# IGVC_breakout_board.net
KiCad netlist of a schematic drawn in EAGLE
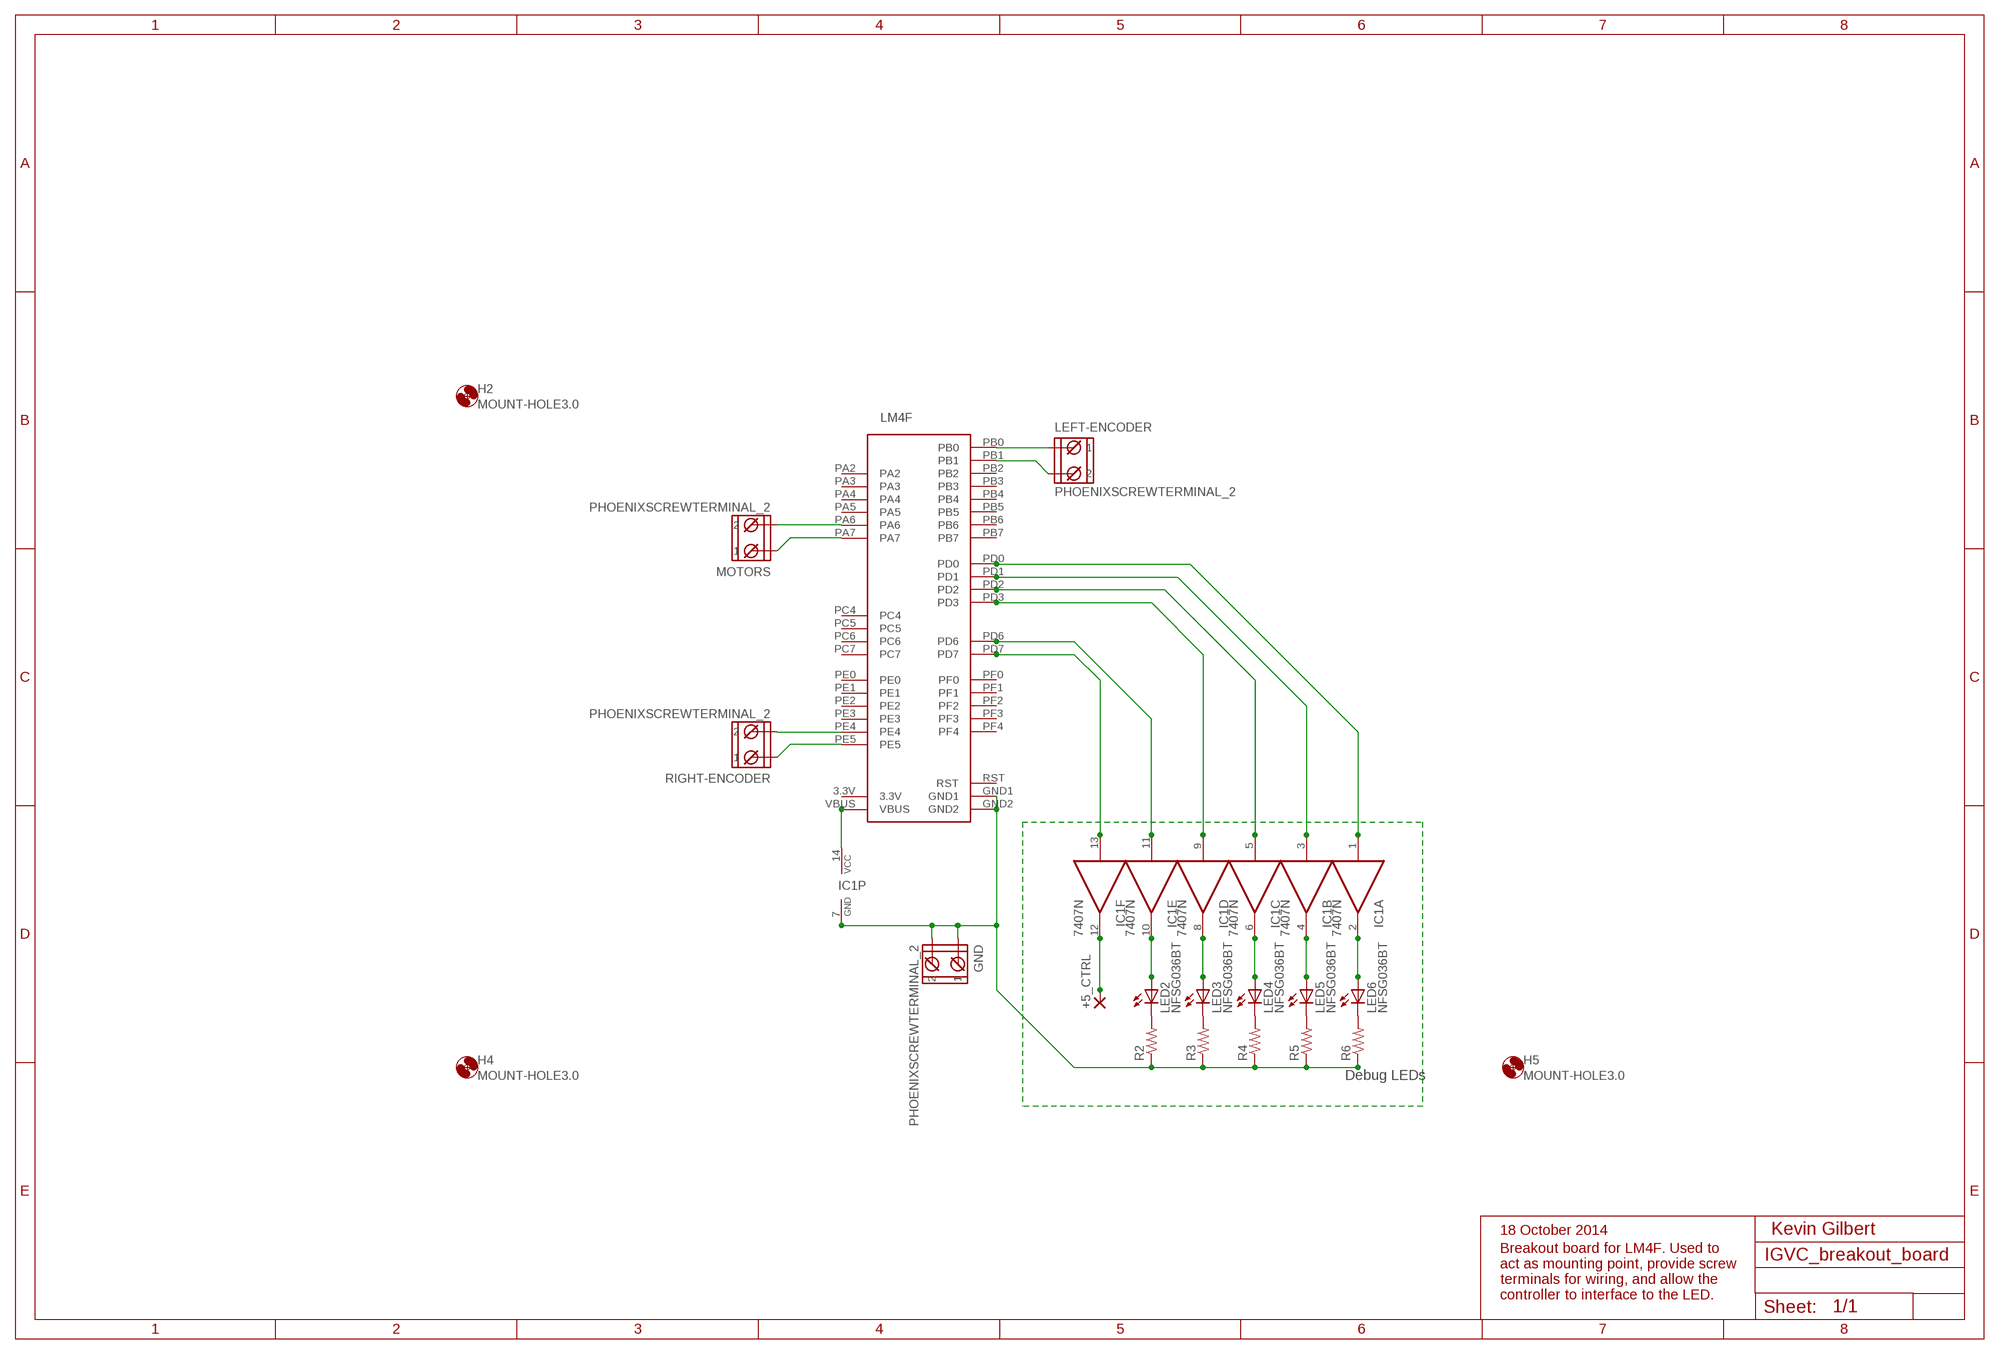
[diagram p0: schematic, sheet 1]

(export (version "E")
  (design (tool "Eeschema 10.0.6"))
  (components
    (comp (ref "+5_CTRL")
      (value "1,6/0,8")
      (footprint "eagle-import:1,6_0,8")
      (libsource (lib "eagle-import") (part "1,6/0,8"))
    )
    (comp (ref "GND")
      (value "PHOENIXSCREWTERMINAL_2")
      (footprint "eagle-import:PHOENIXSCREWTERMINAL_2")
      (libsource (lib "eagle-import") (part "PHOENIXSCREWTERMINAL_2"))
    )
    (comp (ref "H2")
      (value "MOUNT-HOLE3.0")
      (footprint "eagle-import:3,0")
      (libsource (lib "eagle-import") (part "MOUNT-HOLE3.0"))
    )
    (comp (ref "H4")
      (value "MOUNT-HOLE3.0")
      (footprint "eagle-import:3,0")
      (libsource (lib "eagle-import") (part "MOUNT-HOLE3.0"))
    )
    (comp (ref "H5")
      (value "MOUNT-HOLE3.0")
      (footprint "eagle-import:3,0")
      (libsource (lib "eagle-import") (part "MOUNT-HOLE3.0"))
    )
    (comp (ref "IC1")
      (value "7407N")
      (footprint "eagle-import:DIL14")
      (libsource (lib "eagle-import") (part "7407N"))
    )
    (comp (ref "LED2")
      (value "NFSG036BT")
      (footprint "eagle-import:NFSG036BT")
      (libsource (lib "eagle-import") (part "NFSG036BT"))
    )
    (comp (ref "LED3")
      (value "NFSG036BT")
      (footprint "eagle-import:NFSG036BT")
      (libsource (lib "eagle-import") (part "NFSG036BT"))
    )
    (comp (ref "LED4")
      (value "NFSG036BT")
      (footprint "eagle-import:NFSG036BT")
      (libsource (lib "eagle-import") (part "NFSG036BT"))
    )
    (comp (ref "LED5")
      (value "NFSG036BT")
      (footprint "eagle-import:NFSG036BT")
      (libsource (lib "eagle-import") (part "NFSG036BT"))
    )
    (comp (ref "LED6")
      (value "NFSG036BT")
      (footprint "eagle-import:NFSG036BT")
      (libsource (lib "eagle-import") (part "NFSG036BT"))
    )
    (comp (ref "LEFT-ENCODER")
      (value "PHOENIXSCREWTERMINAL_2")
      (footprint "eagle-import:PHOENIXSCREWTERMINAL_2")
      (libsource (lib "eagle-import") (part "PHOENIXSCREWTERMINAL_2"))
    )
    (comp (ref "LM4F")
      (value "STELLARIS-LAUNCHPADSTELLARIS-LAUNCHPAD-XL")
      (footprint "eagle-import:LAUNCHPAD-XL")
      (libsource (lib "eagle-import") (part "STELLARIS-LAUNCHPADSTELLARIS-LAUNCHPAD-XL"))
    )
    (comp (ref "MOTORS")
      (value "PHOENIXSCREWTERMINAL_2")
      (footprint "eagle-import:PHOENIXSCREWTERMINAL_2")
      (libsource (lib "eagle-import") (part "PHOENIXSCREWTERMINAL_2"))
    )
    (comp (ref "R2")
      (value "R-US_M0805")
      (footprint "eagle-import:M0805")
      (libsource (lib "eagle-import") (part "R-US_M0805"))
    )
    (comp (ref "R3")
      (value "R-US_M0805")
      (footprint "eagle-import:M0805")
      (libsource (lib "eagle-import") (part "R-US_M0805"))
    )
    (comp (ref "R4")
      (value "R-US_M0805")
      (footprint "eagle-import:M0805")
      (libsource (lib "eagle-import") (part "R-US_M0805"))
    )
    (comp (ref "R5")
      (value "R-US_M0805")
      (footprint "eagle-import:M0805")
      (libsource (lib "eagle-import") (part "R-US_M0805"))
    )
    (comp (ref "R6")
      (value "R-US_M0805")
      (footprint "eagle-import:M0805")
      (libsource (lib "eagle-import") (part "R-US_M0805"))
    )
    (comp (ref "RIGHT-ENCODER")
      (value "PHOENIXSCREWTERMINAL_2")
      (footprint "eagle-import:PHOENIXSCREWTERMINAL_2")
      (libsource (lib "eagle-import") (part "PHOENIXSCREWTERMINAL_2"))
    )
  )
  (nets
    (net (code "1") (name "/3.3V") (class "Default")
      (node (ref "LM4F") (pin "3.3V") (pinfunction "3.3V_3.3V") (pintype "power_in"))
    )
    (net (code "2") (name "/RST") (class "Default")
      (node (ref "LM4F") (pin "RST") (pinfunction "RST_RST") (pintype "power_in"))
    )
    (net (code "3") (name "Net-(+5_CTRL-P)") (class "Default")
      (node (ref "+5_CTRL") (pin "1") (pinfunction "P_1") (pintype "passive"))
      (node (ref "IC1") (pin "12") (pinfunction "O_12") (pintype "open_collector"))
    )
    (net (code "4") (name "Net-(IC1A-I)") (class "Default")
      (node (ref "IC1") (pin "1") (pinfunction "I_1") (pintype "input"))
      (node (ref "LM4F") (pin "PD0") (pinfunction "PD0_PD0") (pintype "bidirectional"))
    )
    (net (code "5") (name "Net-(IC1A-O)") (class "Default")
      (node (ref "IC1") (pin "2") (pinfunction "O_2") (pintype "open_collector"))
      (node (ref "LED6") (pin "A") (pinfunction "A_A") (pintype "passive"))
    )
    (net (code "6") (name "Net-(IC1B-I)") (class "Default")
      (node (ref "IC1") (pin "3") (pinfunction "I_3") (pintype "input"))
      (node (ref "LM4F") (pin "PD1") (pinfunction "PD1_PD1") (pintype "bidirectional"))
    )
    (net (code "7") (name "Net-(IC1B-O)") (class "Default")
      (node (ref "IC1") (pin "4") (pinfunction "O_4") (pintype "open_collector"))
      (node (ref "LED5") (pin "A") (pinfunction "A_A") (pintype "passive"))
    )
    (net (code "8") (name "Net-(IC1C-I)") (class "Default")
      (node (ref "IC1") (pin "5") (pinfunction "I_5") (pintype "input"))
      (node (ref "LM4F") (pin "PD2") (pinfunction "PD2_PD2") (pintype "bidirectional"))
    )
    (net (code "9") (name "Net-(IC1C-O)") (class "Default")
      (node (ref "IC1") (pin "6") (pinfunction "O_6") (pintype "open_collector"))
      (node (ref "LED4") (pin "A") (pinfunction "A_A") (pintype "passive"))
    )
    (net (code "10") (name "Net-(IC1D-I)") (class "Default")
      (node (ref "IC1") (pin "9") (pinfunction "I_9") (pintype "input"))
      (node (ref "LM4F") (pin "PD3") (pinfunction "PD3_PD3") (pintype "bidirectional"))
    )
    (net (code "11") (name "Net-(IC1D-O)") (class "Default")
      (node (ref "IC1") (pin "8") (pinfunction "O_8") (pintype "open_collector"))
      (node (ref "LED3") (pin "A") (pinfunction "A_A") (pintype "passive"))
    )
    (net (code "12") (name "Net-(IC1E-I)") (class "Default")
      (node (ref "IC1") (pin "11") (pinfunction "I_11") (pintype "input"))
      (node (ref "LM4F") (pin "PD6") (pinfunction "PD6_PD6") (pintype "bidirectional"))
    )
    (net (code "13") (name "Net-(IC1E-O)") (class "Default")
      (node (ref "IC1") (pin "10") (pinfunction "O_10") (pintype "open_collector"))
      (node (ref "LED2") (pin "A") (pinfunction "A_A") (pintype "passive"))
    )
    (net (code "14") (name "Net-(IC1F-I)") (class "Default")
      (node (ref "IC1") (pin "13") (pinfunction "I_13") (pintype "input"))
      (node (ref "LM4F") (pin "PD7") (pinfunction "PD7_PD7") (pintype "bidirectional"))
    )
    (net (code "15") (name "Net-(IC1G-GND)") (class "Default")
      (node (ref "GND") (pin "1") (pinfunction "1_1") (pintype "bidirectional"))
      (node (ref "GND") (pin "2") (pinfunction "2_2") (pintype "bidirectional"))
      (node (ref "IC1") (pin "7") (pinfunction "GND_7") (pintype "power_in"))
      (node (ref "LM4F") (pin "GND1") (pinfunction "GND1_GND1") (pintype "bidirectional"))
      (node (ref "LM4F") (pin "GND2") (pinfunction "GND2_GND2") (pintype "power_in"))
      (node (ref "R2") (pin "1") (pinfunction "1_1") (pintype "passive"))
      (node (ref "R3") (pin "1") (pinfunction "1_1") (pintype "passive"))
      (node (ref "R4") (pin "1") (pinfunction "1_1") (pintype "passive"))
      (node (ref "R5") (pin "1") (pinfunction "1_1") (pintype "passive"))
      (node (ref "R6") (pin "1") (pinfunction "1_1") (pintype "passive"))
    )
    (net (code "16") (name "Net-(IC1G-VCC)") (class "Default")
      (node (ref "IC1") (pin "14") (pinfunction "VCC_14") (pintype "power_in"))
      (node (ref "LM4F") (pin "VBUS") (pinfunction "VBUS_VBUS") (pintype "power_in"))
    )
    (net (code "17") (name "Net-(LED2-PadC)") (class "Default")
      (node (ref "LED2") (pin "C") (pinfunction "C_C") (pintype "passive"))
      (node (ref "R2") (pin "2") (pinfunction "2_2") (pintype "passive"))
    )
    (net (code "18") (name "Net-(LED3-PadC)") (class "Default")
      (node (ref "LED3") (pin "C") (pinfunction "C_C") (pintype "passive"))
      (node (ref "R3") (pin "2") (pinfunction "2_2") (pintype "passive"))
    )
    (net (code "19") (name "Net-(LED4-PadC)") (class "Default")
      (node (ref "LED4") (pin "C") (pinfunction "C_C") (pintype "passive"))
      (node (ref "R4") (pin "2") (pinfunction "2_2") (pintype "passive"))
    )
    (net (code "20") (name "Net-(LED5-PadC)") (class "Default")
      (node (ref "LED5") (pin "C") (pinfunction "C_C") (pintype "passive"))
      (node (ref "R5") (pin "2") (pinfunction "2_2") (pintype "passive"))
    )
    (net (code "21") (name "Net-(LED6-PadC)") (class "Default")
      (node (ref "LED6") (pin "C") (pinfunction "C_C") (pintype "passive"))
      (node (ref "R6") (pin "2") (pinfunction "2_2") (pintype "passive"))
    )
    (net (code "22") (name "Net-(LEFT-ENCODER-Pad1)") (class "Default")
      (node (ref "LEFT-ENCODER") (pin "1") (pinfunction "1_1") (pintype "bidirectional"))
      (node (ref "LM4F") (pin "PB0") (pinfunction "PB0_PB0") (pintype "bidirectional"))
    )
    (net (code "23") (name "Net-(LEFT-ENCODER-Pad2)") (class "Default")
      (node (ref "LEFT-ENCODER") (pin "2") (pinfunction "2_2") (pintype "bidirectional"))
      (node (ref "LM4F") (pin "PB1") (pinfunction "PB1_PB1") (pintype "bidirectional"))
    )
    (net (code "24") (name "Net-(LM4F-PadPA6)") (class "Default")
      (node (ref "LM4F") (pin "PA6") (pinfunction "PA6_PA6") (pintype "bidirectional"))
      (node (ref "MOTORS") (pin "2") (pinfunction "2_2") (pintype "bidirectional"))
    )
    (net (code "25") (name "Net-(LM4F-PadPA7)") (class "Default")
      (node (ref "LM4F") (pin "PA7") (pinfunction "PA7_PA7") (pintype "bidirectional"))
      (node (ref "MOTORS") (pin "1") (pinfunction "1_1") (pintype "bidirectional"))
    )
    (net (code "26") (name "Net-(LM4F-PadPE4)") (class "Default")
      (node (ref "LM4F") (pin "PE4") (pinfunction "PE4_PE4") (pintype "bidirectional"))
      (node (ref "RIGHT-ENCODER") (pin "2") (pinfunction "2_2") (pintype "bidirectional"))
    )
    (net (code "27") (name "Net-(LM4F-PadPE5)") (class "Default")
      (node (ref "LM4F") (pin "PE5") (pinfunction "PE5_PE5") (pintype "bidirectional"))
      (node (ref "RIGHT-ENCODER") (pin "1") (pinfunction "1_1") (pintype "bidirectional"))
    )
    (net (code "28") (name "unconnected-(LM4F-PadPA2)") (class "Default")
      (node (ref "LM4F") (pin "PA2") (pinfunction "PA2_PA2") (pintype "bidirectional"))
    )
    (net (code "29") (name "unconnected-(LM4F-PadPA3)") (class "Default")
      (node (ref "LM4F") (pin "PA3") (pinfunction "PA3_PA3") (pintype "bidirectional"))
    )
    (net (code "30") (name "unconnected-(LM4F-PadPA4)") (class "Default")
      (node (ref "LM4F") (pin "PA4") (pinfunction "PA4_PA4") (pintype "bidirectional"))
    )
    (net (code "31") (name "unconnected-(LM4F-PadPA5)") (class "Default")
      (node (ref "LM4F") (pin "PA5") (pinfunction "PA5_PA5") (pintype "bidirectional"))
    )
    (net (code "32") (name "unconnected-(LM4F-PadPB2)") (class "Default")
      (node (ref "LM4F") (pin "PB2") (pinfunction "PB2_PB2") (pintype "bidirectional"))
    )
    (net (code "33") (name "unconnected-(LM4F-PadPB3)") (class "Default")
      (node (ref "LM4F") (pin "PB3") (pinfunction "PB3_PB3") (pintype "bidirectional"))
    )
    (net (code "34") (name "unconnected-(LM4F-PadPB4)") (class "Default")
      (node (ref "LM4F") (pin "PB4") (pinfunction "PB4_PB4") (pintype "bidirectional"))
    )
    (net (code "35") (name "unconnected-(LM4F-PadPB5)") (class "Default")
      (node (ref "LM4F") (pin "PB5") (pinfunction "PB5_PB5") (pintype "bidirectional"))
    )
    (net (code "36") (name "unconnected-(LM4F-PadPB6)") (class "Default")
      (node (ref "LM4F") (pin "PB6") (pinfunction "PB6_PB6") (pintype "bidirectional"))
    )
    (net (code "37") (name "unconnected-(LM4F-PadPB7)") (class "Default")
      (node (ref "LM4F") (pin "PB7") (pinfunction "PB7_PB7") (pintype "bidirectional"))
    )
    (net (code "38") (name "unconnected-(LM4F-PadPC4)") (class "Default")
      (node (ref "LM4F") (pin "PC4") (pinfunction "PC4_PC4") (pintype "bidirectional"))
    )
    (net (code "39") (name "unconnected-(LM4F-PadPC5)") (class "Default")
      (node (ref "LM4F") (pin "PC5") (pinfunction "PC5_PC5") (pintype "bidirectional"))
    )
    (net (code "40") (name "unconnected-(LM4F-PadPC6)") (class "Default")
      (node (ref "LM4F") (pin "PC6") (pinfunction "PC6_PC6") (pintype "bidirectional"))
    )
    (net (code "41") (name "unconnected-(LM4F-PadPC7)") (class "Default")
      (node (ref "LM4F") (pin "PC7") (pinfunction "PC7_PC7") (pintype "bidirectional"))
    )
    (net (code "42") (name "unconnected-(LM4F-PadPE0)") (class "Default")
      (node (ref "LM4F") (pin "PE0") (pinfunction "PE0_PE0") (pintype "bidirectional"))
    )
    (net (code "43") (name "unconnected-(LM4F-PadPE1)") (class "Default")
      (node (ref "LM4F") (pin "PE1") (pinfunction "PE1_PE1") (pintype "bidirectional"))
    )
    (net (code "44") (name "unconnected-(LM4F-PadPE2)") (class "Default")
      (node (ref "LM4F") (pin "PE2") (pinfunction "PE2_PE2") (pintype "bidirectional"))
    )
    (net (code "45") (name "unconnected-(LM4F-PadPE3)") (class "Default")
      (node (ref "LM4F") (pin "PE3") (pinfunction "PE3_PE3") (pintype "bidirectional"))
    )
    (net (code "46") (name "unconnected-(LM4F-PadPF0)") (class "Default")
      (node (ref "LM4F") (pin "PF0") (pinfunction "PF0_PF0") (pintype "bidirectional"))
    )
    (net (code "47") (name "unconnected-(LM4F-PadPF1)") (class "Default")
      (node (ref "LM4F") (pin "PF1") (pinfunction "PF1_PF1") (pintype "bidirectional"))
    )
    (net (code "48") (name "unconnected-(LM4F-PadPF2)") (class "Default")
      (node (ref "LM4F") (pin "PF2") (pinfunction "PF2_PF2") (pintype "bidirectional"))
    )
    (net (code "49") (name "unconnected-(LM4F-PadPF3)") (class "Default")
      (node (ref "LM4F") (pin "PF3") (pinfunction "PF3_PF3") (pintype "bidirectional"))
    )
    (net (code "50") (name "unconnected-(LM4F-PadPF4)") (class "Default")
      (node (ref "LM4F") (pin "PF4") (pinfunction "PF4_PF4") (pintype "bidirectional"))
    )
  )
)
